# 3_unextended_ISO_mcu.net
KiCad netlist of a schematic drawn in Altium Designer
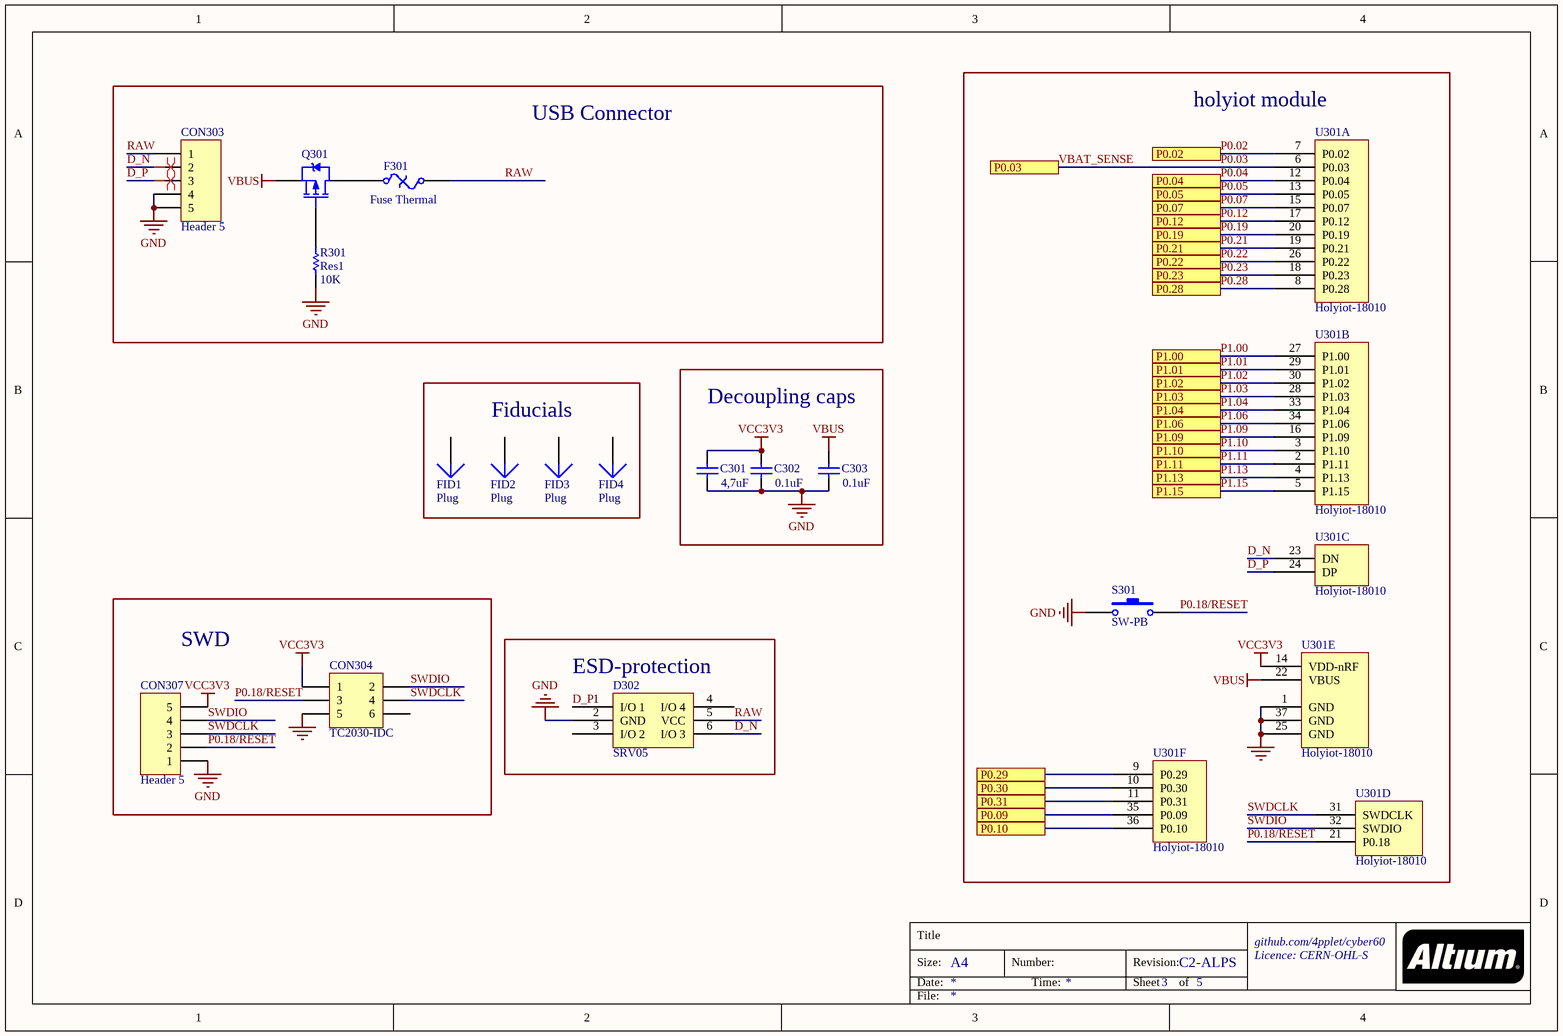
[diagram p0: 3_unextended_ISO_mcu.SchDoc]

(export (version "E")
  (design (tool "Eeschema 10.0.6"))
  (components
    (comp (ref "C301")
      (value "4,7uF")
      (footprint "C0603[1608]")
      (description "Capacitor")
      (fields (field (name "LCSC PART #") "C19666") (field (name "MRF.PART") "CL10A475KO8NNNC"))
      (libsource (lib "Miscellaneous Devices") (part "Cap"))
    )
    (comp (ref "C302")
      (value "0.1uF")
      (footprint "C0603[1608]")
      (description "Capacitor")
      (fields (field (name "MFG") "KEMET") (field (name "LCSC PART #") "C14663"))
      (libsource (lib "Miscellaneous Devices") (part "Cap"))
    )
    (comp (ref "C303")
      (value "0.1uF")
      (footprint "C0603[1608]")
      (description "Capacitor")
      (fields (field (name "MFG") "KEMET") (field (name "LCSC PART #") "C14663"))
      (libsource (lib "Miscellaneous Devices") (part "Cap"))
    )
    (comp (ref "CON303")
      (value "Header 5")
      (footprint "JST SM04B-SRSS-TB")
      (description "JST for USB daughter board")
      (fields (field (name "MFG") "JST Sales America Inc.") (field (name "LCSC PART #") "C160404"))
      (libsource (lib "Miscellaneous Connectors") (part "Header 5"))
    )
    (comp (ref "CON304")
      (value "TC2030-IDC")
      (footprint "TC2030-IDC-NL")
      (description "Header, 3-Pin, Dual row")
      (libsource (lib "Miscellaneous Connectors") (part "Header 3X2"))
    )
    (comp (ref "CON307")
      (value "Header 5")
      (footprint "HDR1X5")
      (description "Header, 5-Pin")
      (libsource (lib "") (part "Header 5_1"))
    )
    (comp (ref "D302")
      (value "SRV05")
      (footprint "SOT-23-6")
      (fields (field (name "LCSC PART #") "C85364") (field (name "MRF.PART") "SRV05-4-P-T7"))
      (libsource (lib "Keebs") (part "SRV05"))
    )
    (comp (ref "F301")
      (value "Fuse Thermal")
      (footprint "C1206[3216]")
      (description "Thermal Fuse")
      (fields (field (name "MFG") "Bel Fuse Inc.") (field (name "LCSC PART #") "C135338"))
      (libsource (lib "Miscellaneous Devices") (part "Fuse Thermal"))
    )
    (comp (ref "FID1")
      (value "Plug")
      (footprint "Fiducial_Nordic")
      (libsource (lib "Miscellaneous Connectors") (part "Plug"))
    )
    (comp (ref "FID2")
      (value "Plug")
      (footprint "Fiducial_Nordic")
      (libsource (lib "Miscellaneous Connectors") (part "Plug"))
    )
    (comp (ref "FID3")
      (value "Plug")
      (footprint "Fiducial_Nordic")
      (libsource (lib "Miscellaneous Connectors") (part "Plug"))
    )
    (comp (ref "FID4")
      (value "Plug")
      (footprint "Fiducial_Nordic")
      (libsource (lib "Miscellaneous Connectors") (part "Plug"))
    )
    (comp (ref "Q301")
      (value "PMOS-2")
      (footprint "SOT-23-3")
      (description "P-Channel Power MOSFET")
      (fields (field (name "LCSC PART #") "C10487") (field (name "MRF.PART") "SI2301CDS-T1-GE3"))
      (libsource (lib "Miscellaneous Devices") (part "PMOS-2"))
    )
    (comp (ref "R301")
      (value "Res1")
      (footprint "R0603[1608]")
      (description "Resistor")
      (fields
        (field (name "ALTIUM_VALUE") "10K")
        (field (name "MFG") "Panasonic Electronic Components")
        (field (name "LCSC PART #") "C25804")
      )
      (libsource (lib "Miscellaneous Devices") (part "Res1"))
    )
    (comp (ref "S301")
      (value "SW-PB")
      (footprint "XKB Switch")
      (description "Switch")
      (fields (field (name "MFG") "C&K") (field (name "MRF.PART") "TS-1187A-C-D-B"))
      (libsource (lib "Miscellaneous Devices") (part "SW-PB"))
    )
    (comp (ref "U301")
      (value "Holyiot-18010")
      (footprint "Holyiot-18010 - outer pads")
      (fields (field (name "MFG") "HolyIOT"))
      (libsource (lib "Keebs") (part "Holyiot-18010"))
    )
  )
  (nets
    (net (code "1") (name "/D_N") (class "Default")
      (node (ref "CON303") (pin "2") (pinfunction "2_2") (pintype "passive"))
      (node (ref "D302") (pin "6") (pinfunction "I/O_3_6") (pintype "passive"))
      (node (ref "U301") (pin "23") (pinfunction "DN_23") (pintype "passive"))
    )
    (net (code "2") (name "/D_P") (class "Default")
      (node (ref "CON303") (pin "3") (pinfunction "3_3") (pintype "passive"))
      (node (ref "D302") (pin "1") (pinfunction "I/O_1_1") (pintype "passive"))
      (node (ref "U301") (pin "24") (pinfunction "DP_24") (pintype "passive"))
    )
    (net (code "3") (name "/P0.02") (class "Default")
      (node (ref "U301") (pin "7") (pinfunction "P0.02_7") (pintype "passive"))
    )
    (net (code "4") (name "/P0.03") (class "Default")
      (node (ref "U301") (pin "6") (pinfunction "P0.03_6") (pintype "passive"))
    )
    (net (code "5") (name "/P0.04") (class "Default")
      (node (ref "U301") (pin "12") (pinfunction "P0.04_12") (pintype "passive"))
    )
    (net (code "6") (name "/P0.05") (class "Default")
      (node (ref "U301") (pin "13") (pinfunction "P0.05_13") (pintype "passive"))
    )
    (net (code "7") (name "/P0.07") (class "Default")
      (node (ref "U301") (pin "15") (pinfunction "P0.07_15") (pintype "passive"))
    )
    (net (code "8") (name "/P0.09") (class "Default")
      (node (ref "U301") (pin "35") (pinfunction "P0.09_35") (pintype "passive"))
    )
    (net (code "9") (name "/P0.10") (class "Default")
      (node (ref "U301") (pin "36") (pinfunction "P0.10_36") (pintype "passive"))
    )
    (net (code "10") (name "/P0.12") (class "Default")
      (node (ref "U301") (pin "17") (pinfunction "P0.12_17") (pintype "passive"))
    )
    (net (code "11") (name "/P0.18{slash}RESET") (class "Default")
      (node (ref "CON304") (pin "3") (pinfunction "3_3") (pintype "passive"))
      (node (ref "CON307") (pin "2") (pinfunction "2_2") (pintype "passive"))
      (node (ref "S301") (pin "2") (pinfunction "2_2") (pintype "passive"))
      (node (ref "U301") (pin "21") (pinfunction "P0.18_21") (pintype "passive"))
    )
    (net (code "12") (name "/P0.19") (class "Default")
      (node (ref "U301") (pin "20") (pinfunction "P0.19_20") (pintype "passive"))
    )
    (net (code "13") (name "/P0.21") (class "Default")
      (node (ref "U301") (pin "19") (pinfunction "P0.21_19") (pintype "passive"))
    )
    (net (code "14") (name "/P0.22") (class "Default")
      (node (ref "U301") (pin "26") (pinfunction "P0.22_26") (pintype "passive"))
    )
    (net (code "15") (name "/P0.23") (class "Default")
      (node (ref "U301") (pin "18") (pinfunction "P0.23_18") (pintype "passive"))
    )
    (net (code "16") (name "/P0.28") (class "Default")
      (node (ref "U301") (pin "8") (pinfunction "P0.28_8") (pintype "passive"))
    )
    (net (code "17") (name "/P0.29") (class "Default")
      (node (ref "U301") (pin "9") (pinfunction "P0.29_9") (pintype "passive"))
    )
    (net (code "18") (name "/P0.30") (class "Default")
      (node (ref "U301") (pin "10") (pinfunction "P0.30_10") (pintype "passive"))
    )
    (net (code "19") (name "/P0.31") (class "Default")
      (node (ref "U301") (pin "11") (pinfunction "P0.31_11") (pintype "passive"))
    )
    (net (code "20") (name "/P1.00") (class "Default")
      (node (ref "U301") (pin "27") (pinfunction "P1.00_27") (pintype "passive"))
    )
    (net (code "21") (name "/P1.01") (class "Default")
      (node (ref "U301") (pin "29") (pinfunction "P1.01_29") (pintype "passive"))
    )
    (net (code "22") (name "/P1.02") (class "Default")
      (node (ref "U301") (pin "30") (pinfunction "P1.02_30") (pintype "passive"))
    )
    (net (code "23") (name "/P1.03") (class "Default")
      (node (ref "U301") (pin "28") (pinfunction "P1.03_28") (pintype "passive"))
    )
    (net (code "24") (name "/P1.04") (class "Default")
      (node (ref "U301") (pin "33") (pinfunction "P1.04_33") (pintype "passive"))
    )
    (net (code "25") (name "/P1.06") (class "Default")
      (node (ref "U301") (pin "34") (pinfunction "P1.06_34") (pintype "passive"))
    )
    (net (code "26") (name "/P1.09") (class "Default")
      (node (ref "U301") (pin "16") (pinfunction "P1.09_16") (pintype "passive"))
    )
    (net (code "27") (name "/P1.10") (class "Default")
      (node (ref "U301") (pin "3") (pinfunction "P1.10_3") (pintype "passive"))
    )
    (net (code "28") (name "/P1.11") (class "Default")
      (node (ref "U301") (pin "2") (pinfunction "P1.11_2") (pintype "passive"))
    )
    (net (code "29") (name "/P1.13") (class "Default")
      (node (ref "U301") (pin "4") (pinfunction "P1.13_4") (pintype "passive"))
    )
    (net (code "30") (name "/P1.15") (class "Default")
      (node (ref "U301") (pin "5") (pinfunction "P1.15_5") (pintype "passive"))
    )
    (net (code "31") (name "/RAW") (class "Default")
      (node (ref "CON303") (pin "1") (pinfunction "1_1") (pintype "passive"))
      (node (ref "D302") (pin "5") (pinfunction "VCC_5") (pintype "passive"))
      (node (ref "F301") (pin "2") (pinfunction "2_2") (pintype "passive"))
    )
    (net (code "32") (name "/SWDCLK") (class "Default")
      (node (ref "CON304") (pin "4") (pinfunction "4_4") (pintype "passive"))
      (node (ref "CON307") (pin "3") (pinfunction "3_3") (pintype "passive"))
      (node (ref "U301") (pin "31") (pinfunction "SWDCLK_31") (pintype "passive"))
    )
    (net (code "33") (name "/SWDIO") (class "Default")
      (node (ref "CON304") (pin "2") (pinfunction "2_2") (pintype "passive"))
      (node (ref "CON307") (pin "4") (pinfunction "4_4") (pintype "passive"))
      (node (ref "U301") (pin "32") (pinfunction "SWDIO_32") (pintype "passive"))
    )
    (net (code "34") (name "GND") (class "Default")
      (node (ref "C301") (pin "1") (pinfunction "1_1") (pintype "passive"))
      (node (ref "C302") (pin "1") (pinfunction "1_1") (pintype "passive"))
      (node (ref "C303") (pin "1") (pinfunction "1_1") (pintype "passive"))
      (node (ref "CON303") (pin "4") (pinfunction "4_4") (pintype "passive"))
      (node (ref "CON303") (pin "5") (pinfunction "5_5") (pintype "passive"))
      (node (ref "CON304") (pin "5") (pinfunction "5_5") (pintype "passive"))
      (node (ref "CON307") (pin "1") (pinfunction "1_1") (pintype "passive"))
      (node (ref "D302") (pin "2") (pinfunction "GND_2") (pintype "passive"))
      (node (ref "R301") (pin "2") (pinfunction "2_2") (pintype "passive"))
      (node (ref "S301") (pin "1") (pinfunction "1_1") (pintype "passive"))
      (node (ref "U301") (pin "1") (pinfunction "GND_1") (pintype "passive"))
      (node (ref "U301") (pin "25") (pinfunction "GND_25") (pintype "passive"))
      (node (ref "U301") (pin "37") (pinfunction "GND_37") (pintype "passive"))
    )
    (net (code "35") (name "Net-(Q301-D)") (class "Default")
      (node (ref "F301") (pin "1") (pinfunction "1_1") (pintype "passive"))
      (node (ref "Q301") (pin "3") (pinfunction "D_3") (pintype "passive"))
    )
    (net (code "36") (name "Net-(Q301-G)") (class "Default")
      (node (ref "Q301") (pin "1") (pinfunction "G_1") (pintype "passive"))
      (node (ref "R301") (pin "1") (pinfunction "1_1") (pintype "passive"))
    )
    (net (code "37") (name "VBUS") (class "Default")
      (node (ref "C303") (pin "2") (pinfunction "2_2") (pintype "passive"))
      (node (ref "Q301") (pin "2") (pinfunction "S_2") (pintype "passive"))
      (node (ref "U301") (pin "22") (pinfunction "VBUS_22") (pintype "passive"))
    )
    (net (code "38") (name "VCC3V3") (class "Default")
      (node (ref "C301") (pin "2") (pinfunction "2_2") (pintype "passive"))
      (node (ref "C302") (pin "2") (pinfunction "2_2") (pintype "passive"))
      (node (ref "CON304") (pin "1") (pinfunction "1_1") (pintype "passive"))
      (node (ref "CON307") (pin "5") (pinfunction "5_5") (pintype "passive"))
      (node (ref "U301") (pin "14") (pinfunction "VDD-nRF_14") (pintype "passive"))
    )
    (net (code "39") (name "unconnected-(CON304-Pad6)") (class "Default")
      (node (ref "CON304") (pin "6") (pinfunction "6_6") (pintype "passive"))
    )
    (net (code "40") (name "unconnected-(D302-I{slash}O_2-Pad3)") (class "Default")
      (node (ref "D302") (pin "3") (pinfunction "I/O_2_3") (pintype "passive"))
    )
    (net (code "41") (name "unconnected-(D302-I{slash}O_4-Pad4)") (class "Default")
      (node (ref "D302") (pin "4") (pinfunction "I/O_4_4") (pintype "passive"))
    )
    (net (code "42") (name "unconnected-(FID1-Pad1)") (class "Default")
      (node (ref "FID1") (pin "1") (pinfunction "1_1") (pintype "passive"))
    )
    (net (code "43") (name "unconnected-(FID2-Pad1)") (class "Default")
      (node (ref "FID2") (pin "1") (pinfunction "1_1") (pintype "passive"))
    )
    (net (code "44") (name "unconnected-(FID3-Pad1)") (class "Default")
      (node (ref "FID3") (pin "1") (pinfunction "1_1") (pintype "passive"))
    )
    (net (code "45") (name "unconnected-(FID4-Pad1)") (class "Default")
      (node (ref "FID4") (pin "1") (pinfunction "1_1") (pintype "passive"))
    )
  )
)
